# Nosumor.net
KiCad netlist of a schematic drawn in EAGLE
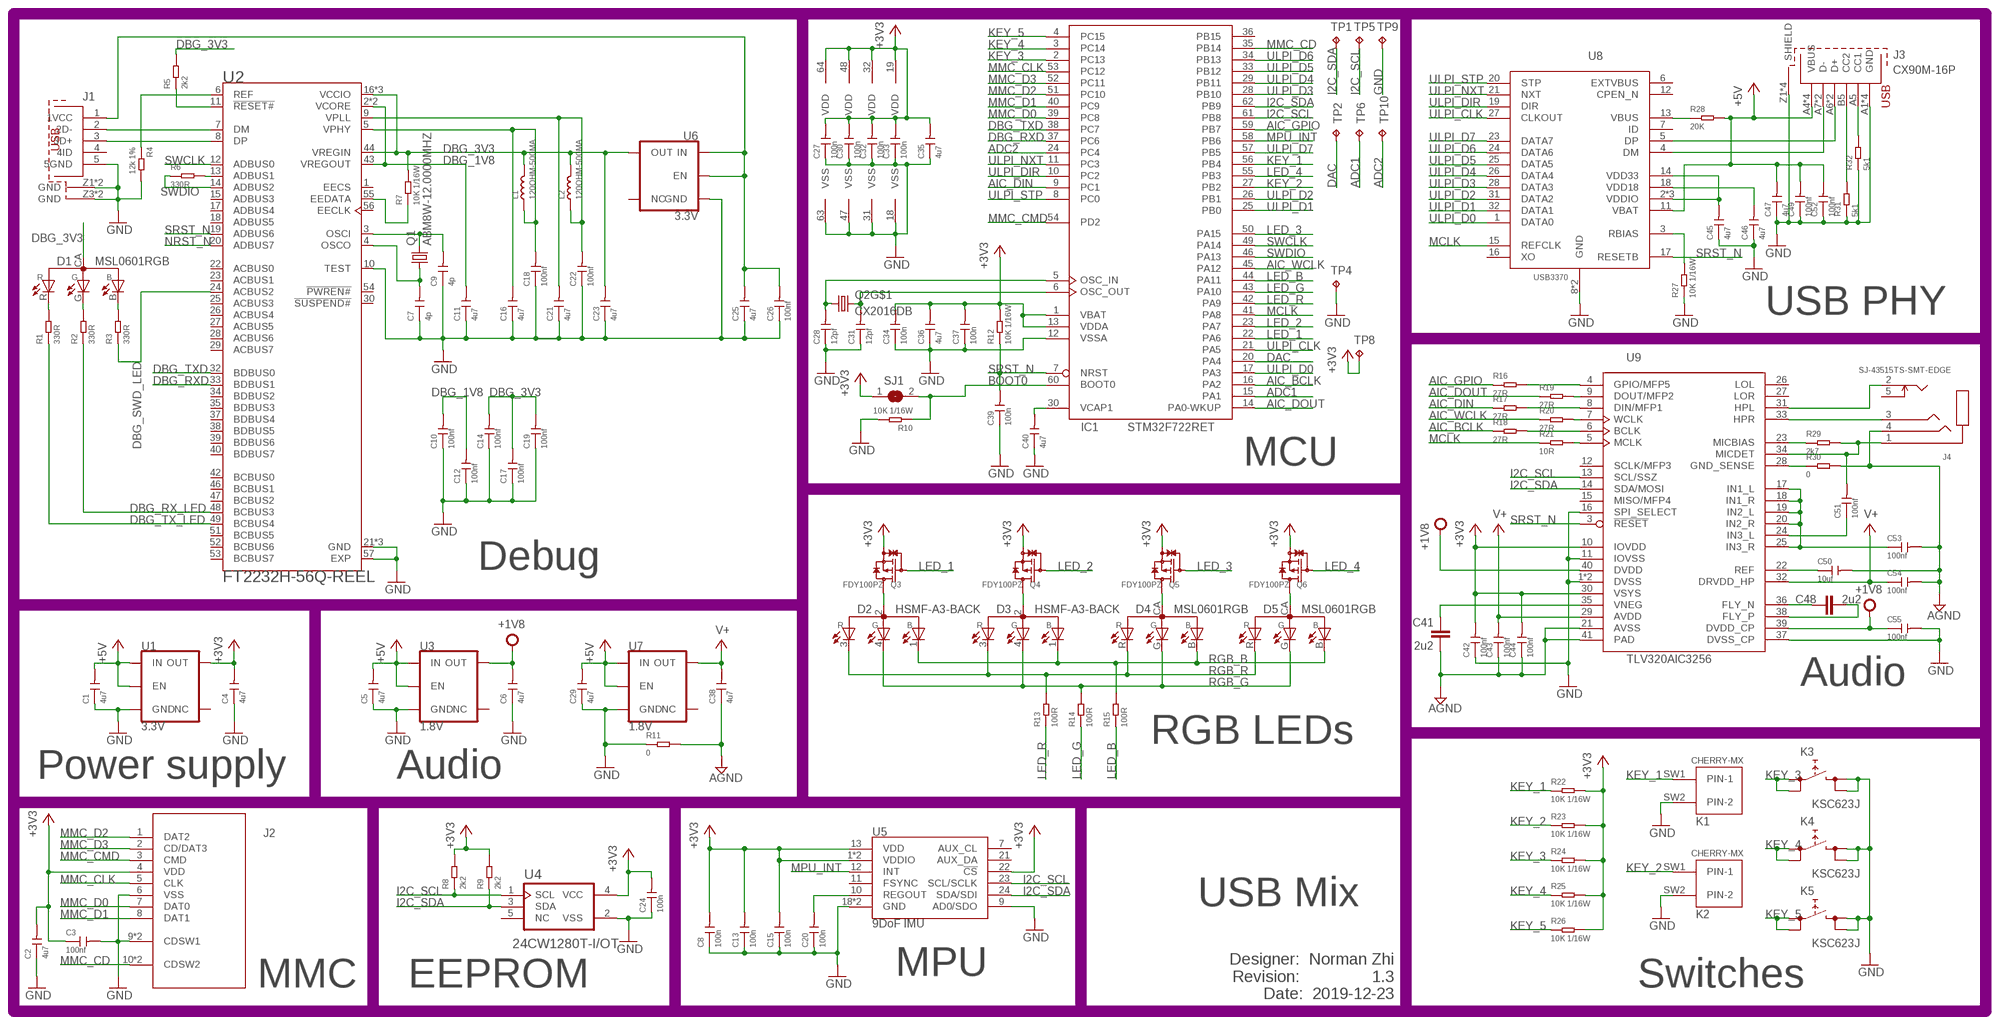
[diagram p0: schematic, sheet 1]

(export (version "E")
  (design (tool "Eeschema 10.0.6"))
  (components
    (comp (ref "C1")
      (value "4u7")
      (footprint "eagle-import:C0402")
      (fields (field (name "MPN") "CC0402KRX5R5BB105"))
      (libsource (lib "eagle-import") (part "CERAMIC-1UF-6.3V-10%-X5R(0402)"))
    )
    (comp (ref "C2")
      (value "4u7")
      (footprint "eagle-import:C0402")
      (fields (field (name "MPN") "CC0402KRX5R5BB105"))
      (libsource (lib "eagle-import") (part "CERAMIC-1UF-6.3V-10%-X5R(0402)"))
    )
    (comp (ref "C3")
      (value "100nf")
      (footprint "eagle-import:C0402")
      (fields (field (name "MPN") "CC0402KRX7R8BB104"))
      (libsource (lib "eagle-import") (part "CERAMIC-100NF-25V-10%-X7R(0402)"))
    )
    (comp (ref "C4")
      (value "4u7")
      (footprint "eagle-import:C0402")
      (fields (field (name "MPN") "CC0402KRX5R5BB105"))
      (libsource (lib "eagle-import") (part "CERAMIC-1UF-6.3V-10%-X5R(0402)"))
    )
    (comp (ref "C5")
      (value "4u7")
      (footprint "eagle-import:C0402")
      (fields (field (name "MPN") "CC0402KRX5R5BB105"))
      (libsource (lib "eagle-import") (part "CERAMIC-1UF-6.3V-10%-X5R(0402)"))
    )
    (comp (ref "C6")
      (value "4u7")
      (footprint "eagle-import:C0402")
      (fields (field (name "MPN") "CC0402KRX5R5BB105"))
      (libsource (lib "eagle-import") (part "CERAMIC-1UF-6.3V-10%-X5R(0402)"))
    )
    (comp (ref "C7")
      (value "4p")
      (footprint "eagle-import:C0402")
      (fields (field (name "MPN") "CC0402KRX7R8BB104"))
      (libsource (lib "eagle-import") (part "CERAMIC-100NF-25V-10%-X7R(0402)"))
    )
    (comp (ref "C8")
      (value "100n")
      (footprint "eagle-import:C0402")
      (fields (field (name "MPN") "CC0402KRX7R8BB104"))
      (libsource (lib "eagle-import") (part "CERAMIC-100NF-25V-10%-X7R(0402)"))
    )
    (comp (ref "C9")
      (value "4p")
      (footprint "eagle-import:C0402")
      (fields (field (name "MPN") "CC0402KRX7R8BB104"))
      (libsource (lib "eagle-import") (part "CERAMIC-100NF-25V-10%-X7R(0402)"))
    )
    (comp (ref "C10")
      (value "100nf")
      (footprint "eagle-import:C0402")
      (fields (field (name "MPN") "CC0402KRX7R8BB104"))
      (libsource (lib "eagle-import") (part "CERAMIC-100NF-25V-10%-X7R(0402)"))
    )
    (comp (ref "C11")
      (value "4u7")
      (footprint "eagle-import:C0402")
      (fields (field (name "MPN") "CC0402KRX7R8BB104"))
      (libsource (lib "eagle-import") (part "CERAMIC-100NF-25V-10%-X7R(0402)"))
    )
    (comp (ref "C12")
      (value "100nf")
      (footprint "eagle-import:C0402")
      (fields (field (name "MPN") "CC0402KRX7R8BB104"))
      (libsource (lib "eagle-import") (part "CERAMIC-100NF-25V-10%-X7R(0402)"))
    )
    (comp (ref "C13")
      (value "100n")
      (footprint "eagle-import:C0402")
      (fields (field (name "MPN") "CC0402KRX7R8BB104"))
      (libsource (lib "eagle-import") (part "CERAMIC-100NF-25V-10%-X7R(0402)"))
    )
    (comp (ref "C14")
      (value "100nf")
      (footprint "eagle-import:C0402")
      (fields (field (name "MPN") "CC0402KRX7R8BB104"))
      (libsource (lib "eagle-import") (part "CERAMIC-100NF-25V-10%-X7R(0402)"))
    )
    (comp (ref "C15")
      (value "100n")
      (footprint "eagle-import:C0402")
      (fields (field (name "MPN") "CC0402KRX7R9BB103"))
      (libsource (lib "eagle-import") (part "CERAMIC-10NF-50V-10%-X7R(0402)"))
    )
    (comp (ref "C16")
      (value "4u7")
      (footprint "eagle-import:C0402")
      (fields (field (name "MPN") "CC0402KRX7R8BB104"))
      (libsource (lib "eagle-import") (part "CERAMIC-100NF-25V-10%-X7R(0402)"))
    )
    (comp (ref "C17")
      (value "100nf")
      (footprint "eagle-import:C0402")
      (fields (field (name "MPN") "CC0402KRX7R8BB104"))
      (libsource (lib "eagle-import") (part "CERAMIC-100NF-25V-10%-X7R(0402)"))
    )
    (comp (ref "C18")
      (value "100nf")
      (footprint "eagle-import:C0402")
      (fields (field (name "MPN") "CC0402KRX7R8BB104"))
      (libsource (lib "eagle-import") (part "CERAMIC-100NF-25V-10%-X7R(0402)"))
    )
    (comp (ref "C19")
      (value "100nf")
      (footprint "eagle-import:C0402")
      (fields (field (name "MPN") "CC0402KRX7R8BB104"))
      (libsource (lib "eagle-import") (part "CERAMIC-100NF-25V-10%-X7R(0402)"))
    )
    (comp (ref "C20")
      (value "100n")
      (footprint "eagle-import:C0402")
      (fields (field (name "MPN") "CC0402KRX7R8BB104"))
      (libsource (lib "eagle-import") (part "CERAMIC-100NF-25V-10%-X7R(0402)"))
    )
    (comp (ref "C21")
      (value "4u7")
      (footprint "eagle-import:C0402")
      (fields (field (name "MPN") "CC0402KRX7R8BB104"))
      (libsource (lib "eagle-import") (part "CERAMIC-100NF-25V-10%-X7R(0402)"))
    )
    (comp (ref "C22")
      (value "100nf")
      (footprint "eagle-import:C0402")
      (fields (field (name "MPN") "CC0402KRX7R8BB104"))
      (libsource (lib "eagle-import") (part "CERAMIC-100NF-25V-10%-X7R(0402)"))
    )
    (comp (ref "C23")
      (value "4u7")
      (footprint "eagle-import:C0402")
      (fields (field (name "MPN") "CC0402KRX5R5BB105"))
      (libsource (lib "eagle-import") (part "CERAMIC-1UF-6.3V-10%-X5R(0402)"))
    )
    (comp (ref "C24")
      (value "100n")
      (footprint "eagle-import:C0402")
      (fields (field (name "MPN") "CC0402KRX7R8BB104"))
      (libsource (lib "eagle-import") (part "CERAMIC-100NF-25V-10%-X7R(0402)"))
    )
    (comp (ref "C25")
      (value "4u7")
      (footprint "eagle-import:C0402")
      (fields (field (name "MPN") "CC0402KRX5R5BB105"))
      (libsource (lib "eagle-import") (part "CERAMIC-1UF-6.3V-10%-X5R(0402)"))
    )
    (comp (ref "C26")
      (value "100nf")
      (footprint "eagle-import:C0402")
      (fields (field (name "MPN") "CC0402KRX7R8BB104"))
      (libsource (lib "eagle-import") (part "CERAMIC-100NF-25V-10%-X7R(0402)"))
    )
    (comp (ref "C27")
      (value "100n")
      (footprint "eagle-import:C0402")
      (fields (field (name "MPN") "CC0402KRX7R8BB104"))
      (libsource (lib "eagle-import") (part "CERAMIC-100NF-25V-10%-X7R(0402)"))
    )
    (comp (ref "C28")
      (value "12pf")
      (footprint "eagle-import:C0402")
      (fields (field (name "MPN") "CC0402JRNPO9BN120"))
      (libsource (lib "eagle-import") (part "CERAMIC-12PF-50V-5%-NPO(0402)"))
    )
    (comp (ref "C29")
      (value "4u7")
      (footprint "eagle-import:C0402")
      (fields (field (name "MPN") "CC0402KRX5R5BB105"))
      (libsource (lib "eagle-import") (part "CERAMIC-1UF-6.3V-10%-X5R(0402)"))
    )
    (comp (ref "C30")
      (value "100n")
      (footprint "eagle-import:C0402")
      (fields (field (name "MPN") "CC0402KRX7R8BB104"))
      (libsource (lib "eagle-import") (part "CERAMIC-100NF-25V-10%-X7R(0402)"))
    )
    (comp (ref "C31")
      (value "12pf")
      (footprint "eagle-import:C0402")
      (fields (field (name "MPN") "CC0402JRNPO9BN120"))
      (libsource (lib "eagle-import") (part "CERAMIC-12PF-50V-5%-NPO(0402)"))
    )
    (comp (ref "C32")
      (value "100n")
      (footprint "eagle-import:C0402")
      (fields (field (name "MPN") "CC0402KRX7R8BB104"))
      (libsource (lib "eagle-import") (part "CERAMIC-100NF-25V-10%-X7R(0402)"))
    )
    (comp (ref "C33")
      (value "100n")
      (footprint "eagle-import:C0402")
      (fields (field (name "MPN") "CC0402KRX7R8BB104"))
      (libsource (lib "eagle-import") (part "CERAMIC-100NF-25V-10%-X7R(0402)"))
    )
    (comp (ref "C34")
      (value "100n")
      (footprint "eagle-import:C0402")
      (fields (field (name "MPN") "CC0402KRX7R9BB103"))
      (libsource (lib "eagle-import") (part "CERAMIC-10NF-50V-10%-X7R(0402)"))
    )
    (comp (ref "C35")
      (value "4u7")
      (footprint "eagle-import:C0603")
      (fields (field (name "MPN") "CC0603KRX5R6BB475"))
      (libsource (lib "eagle-import") (part "CERAMIC-4.7UF-10V-10%-X5R(0603)"))
    )
    (comp (ref "C36")
      (value "4u7")
      (footprint "eagle-import:C0603")
      (fields (field (name "MPN") "CC0603KRX5R6BB475"))
      (libsource (lib "eagle-import") (part "CERAMIC-4.7UF-10V-10%-X5R(0603)"))
    )
    (comp (ref "C37")
      (value "100n")
      (footprint "eagle-import:C0402")
      (fields (field (name "MPN") "CC0402KRX7R8BB104"))
      (libsource (lib "eagle-import") (part "CERAMIC-100NF-25V-10%-X7R(0402)"))
    )
    (comp (ref "C38")
      (value "4u7")
      (footprint "eagle-import:C0402")
      (fields (field (name "MPN") "CC0402KRX5R5BB105"))
      (libsource (lib "eagle-import") (part "CERAMIC-1UF-6.3V-10%-X5R(0402)"))
    )
    (comp (ref "C39")
      (value "100n")
      (footprint "eagle-import:C0402")
      (fields (field (name "MPN") "CC0402KRX7R8BB104"))
      (libsource (lib "eagle-import") (part "CERAMIC-100NF-25V-10%-X7R(0402)"))
    )
    (comp (ref "C40")
      (value "4u7")
      (footprint "eagle-import:C0603")
      (fields (field (name "MPN") "CC0603KRX5R6BB475"))
      (libsource (lib "eagle-import") (part "CERAMIC-4.7UF-10V-10%-X5R(0603)"))
    )
    (comp (ref "C41")
      (value "2u2")
      (footprint "eagle-import:C0603K")
      (libsource (lib "eagle-import") (part "C-EUC0603K"))
    )
    (comp (ref "C42")
      (value "100nf")
      (footprint "eagle-import:C0402")
      (fields (field (name "MPN") "CC0402KRX7R8BB104"))
      (libsource (lib "eagle-import") (part "CERAMIC-100NF-25V-10%-X7R(0402)"))
    )
    (comp (ref "C43")
      (value "100nf")
      (footprint "eagle-import:C0402")
      (fields (field (name "MPN") "CC0402KRX7R8BB104"))
      (libsource (lib "eagle-import") (part "CERAMIC-100NF-25V-10%-X7R(0402)"))
    )
    (comp (ref "C44")
      (value "100nf")
      (footprint "eagle-import:C0402")
      (fields (field (name "MPN") "CC0402KRX7R8BB104"))
      (libsource (lib "eagle-import") (part "CERAMIC-100NF-25V-10%-X7R(0402)"))
    )
    (comp (ref "C45")
      (value "4u7")
      (footprint "eagle-import:C0402")
      (fields (field (name "MPN") "CC0402KRX5R5BB105"))
      (libsource (lib "eagle-import") (part "CERAMIC-1UF-6.3V-10%-X5R(0402)"))
    )
    (comp (ref "C46")
      (value "4u7")
      (footprint "eagle-import:C0402")
      (fields (field (name "MPN") "CC0402KRX5R5BB105"))
      (libsource (lib "eagle-import") (part "CERAMIC-1UF-6.3V-10%-X5R(0402)"))
    )
    (comp (ref "C47")
      (value "4u7")
      (footprint "eagle-import:C0402")
      (fields (field (name "MPN") "CC0402KRX5R5BB105"))
      (libsource (lib "eagle-import") (part "CERAMIC-1UF-6.3V-10%-X5R(0402)"))
    )
    (comp (ref "C48")
      (value "2u2")
      (footprint "eagle-import:C0603K")
      (libsource (lib "eagle-import") (part "C-EUC0603K"))
    )
    (comp (ref "C49")
      (value "100nf")
      (footprint "eagle-import:C0402")
      (fields (field (name "MPN") "CC0402KRX7R8BB104"))
      (libsource (lib "eagle-import") (part "CERAMIC-100NF-25V-10%-X7R(0402)"))
    )
    (comp (ref "C50")
      (value "10uf")
      (footprint "eagle-import:C0603")
      (fields (field (name "MPN") "CC0603KRX5R6BB106"))
      (libsource (lib "eagle-import") (part "CERAMIC-10UF-10V-10%-X5R(0603)"))
    )
    (comp (ref "C51")
      (value "100nf")
      (footprint "eagle-import:C0402")
      (fields (field (name "MPN") "CC0402KRX7R8BB104"))
      (libsource (lib "eagle-import") (part "CERAMIC-100NF-25V-10%-X7R(0402)"))
    )
    (comp (ref "C52")
      (value "100nf")
      (footprint "eagle-import:C0402")
      (fields (field (name "MPN") "CC0402KRX7R8BB104"))
      (libsource (lib "eagle-import") (part "CERAMIC-100NF-25V-10%-X7R(0402)"))
    )
    (comp (ref "C53")
      (value "100nf")
      (footprint "eagle-import:C0402")
      (fields (field (name "MPN") "CC0402KRX7R8BB104"))
      (libsource (lib "eagle-import") (part "CERAMIC-100NF-25V-10%-X7R(0402)"))
    )
    (comp (ref "C54")
      (value "100nf")
      (footprint "eagle-import:C0402")
      (fields (field (name "MPN") "CC0402KRX7R8BB104"))
      (libsource (lib "eagle-import") (part "CERAMIC-100NF-25V-10%-X7R(0402)"))
    )
    (comp (ref "C55")
      (value "100nf")
      (footprint "eagle-import:C0402")
      (fields (field (name "MPN") "CC0402KRX7R8BB104"))
      (libsource (lib "eagle-import") (part "CERAMIC-100NF-25V-10%-X7R(0402)"))
    )
    (comp (ref "D1")
      (value "MSL0601RGB")
      (footprint "eagle-import:1105")
      (libsource (lib "eagle-import") (part "MSL0601RGB"))
    )
    (comp (ref "D2")
      (value "HSMF-A3-BACK")
      (footprint "eagle-import:HSMF-A3-BACK")
      (libsource (lib "eagle-import") (part "HSMF-A3-BACK"))
    )
    (comp (ref "D3")
      (value "HSMF-A3-BACK")
      (footprint "eagle-import:HSMF-A3-BACK")
      (libsource (lib "eagle-import") (part "HSMF-A3-BACK"))
    )
    (comp (ref "D4")
      (value "MSL0601RGB")
      (footprint "eagle-import:1105")
      (libsource (lib "eagle-import") (part "MSL0601RGB"))
    )
    (comp (ref "D5")
      (value "MSL0601RGB")
      (footprint "eagle-import:1105")
      (libsource (lib "eagle-import") (part "MSL0601RGB"))
    )
    (comp (ref "IC1")
      (value "STM32F722RET")
      (footprint "eagle-import:LQFP64")
      (libsource (lib "eagle-import") (part "STM32F722RTE"))
    )
    (comp (ref "J1")
      (value "629105150521")
      (footprint "eagle-import:629105150521")
      (libsource (lib "eagle-import") (part "629105150521"))
    )
    (comp (ref "J2")
      (value "693071010811")
      (footprint "eagle-import:693071010811")
      (libsource (lib "eagle-import") (part "693071010811"))
    )
    (comp (ref "J3")
      (value "CX90M-16P")
      (footprint "eagle-import:CX90M-16P")
      (libsource (lib "eagle-import") (part "CX90M-16P"))
    )
    (comp (ref "J4")
      (value "SJ-43515TS-SMT-EDGE")
      (footprint "eagle-import:SJ-4351_-SMT-MIRRORED-EDGE")
      (libsource (lib "eagle-import") (part "SJ-43515TS-SMT-EDGE"))
    )
    (comp (ref "K1")
      (value "CHERRY-MX")
      (footprint "eagle-import:CHERRY-MX")
      (libsource (lib "eagle-import") (part "CHERRY-MX"))
    )
    (comp (ref "K2")
      (value "CHERRY-MX")
      (footprint "eagle-import:CHERRY-MX")
      (libsource (lib "eagle-import") (part "CHERRY-MX"))
    )
    (comp (ref "K3")
      (value "KSC623J")
      (footprint "eagle-import:KSC-J")
      (libsource (lib "eagle-import") (part "KSCJ623"))
    )
    (comp (ref "K4")
      (value "KSC623J")
      (footprint "eagle-import:KSC-J")
      (libsource (lib "eagle-import") (part "KSCJ623"))
    )
    (comp (ref "K5")
      (value "KSC623J")
      (footprint "eagle-import:KSC-J")
      (libsource (lib "eagle-import") (part "KSCJ623"))
    )
    (comp (ref "L1")
      (value "120OHM-500MA")
      (footprint "eagle-import:L0603")
      (fields (field (name "MPN") "BLM18AG121SN1D"))
      (libsource (lib "eagle-import") (part "SMD-FERRITE-CHIP-120-OHM-500MA(0603)"))
    )
    (comp (ref "L2")
      (value "120OHM-500MA")
      (footprint "eagle-import:L0603")
      (fields (field (name "MPN") "BLM18AG121SN1D"))
      (libsource (lib "eagle-import") (part "SMD-FERRITE-CHIP-120-OHM-500MA(0603)"))
    )
    (comp (ref "Q1")
      (value "ABM8W-12.0000MHZ")
      (footprint "eagle-import:ABM8W")
      (libsource (lib "eagle-import") (part "ABM?-MHZ8W12.0000"))
    )
    (comp (ref "Q2")
      (value "CX2016DB")
      (footprint "eagle-import:CX2016DB")
      (libsource (lib "eagle-import") (part "CX2016DB"))
    )
    (comp (ref "Q3")
      (value "FDY100PZ")
      (footprint "eagle-import:SC-89")
      (libsource (lib "eagle-import") (part "FDY100PZ"))
    )
    (comp (ref "Q4")
      (value "FDY100PZ")
      (footprint "eagle-import:SC-89")
      (libsource (lib "eagle-import") (part "FDY100PZ"))
    )
    (comp (ref "Q5")
      (value "FDY100PZ")
      (footprint "eagle-import:SC-89")
      (libsource (lib "eagle-import") (part "FDY100PZ"))
    )
    (comp (ref "Q6")
      (value "FDY100PZ")
      (footprint "eagle-import:SC-89")
      (libsource (lib "eagle-import") (part "FDY100PZ"))
    )
    (comp (ref "R1")
      (value "330R")
      (footprint "eagle-import:R0402")
      (fields (field (name "MPN") "RC0402FR-07330RL"))
      (libsource (lib "eagle-import") (part "SMD-RES-330R-1%-1/16W(0402)"))
    )
    (comp (ref "R2")
      (value "330R")
      (footprint "eagle-import:R0402")
      (fields (field (name "MPN") "RC0402FR-07330RL"))
      (libsource (lib "eagle-import") (part "SMD-RES-330R-1%-1/16W(0402)"))
    )
    (comp (ref "R3")
      (value "330R")
      (footprint "eagle-import:R0402")
      (fields (field (name "MPN") "RC0402FR-07330RL"))
      (libsource (lib "eagle-import") (part "SMD-RES-330R-1%-1/16W(0402)"))
    )
    (comp (ref "R4")
      (value "12k 1%")
      (footprint "eagle-import:R0402")
      (fields (field (name "MPN") "RC0402FR-0710KL"))
      (libsource (lib "eagle-import") (part "SMD-RES-10K-1%-1/16W(0402)"))
    )
    (comp (ref "R5")
      (value "2k2")
      (footprint "eagle-import:R0402")
      (fields (field (name "MPN") "RC0402FR-0710KL"))
      (libsource (lib "eagle-import") (part "SMD-RES-10K-1%-1/16W(0402)"))
    )
    (comp (ref "R6")
      (value "330R")
      (footprint "eagle-import:R0402")
      (fields (field (name "MPN") "RC0402JR-07470RL"))
      (libsource (lib "eagle-import") (part "SMD-RES-470R-5%-1/16W(0402)"))
    )
    (comp (ref "R7")
      (value "10K 1/16W")
      (footprint "eagle-import:R0402")
      (fields (field (name "MPN") "RC0402FR-0710KL"))
      (libsource (lib "eagle-import") (part "SMD-RES-10K-1%-1/16W(0402)"))
    )
    (comp (ref "R8")
      (value "2k2")
      (footprint "eagle-import:R0402")
      (fields (field (name "MPN") "RC0402FR-0710KL"))
      (libsource (lib "eagle-import") (part "SMD-RES-10K-1%-1/16W(0402)"))
    )
    (comp (ref "R9")
      (value "2k2")
      (footprint "eagle-import:R0402")
      (fields (field (name "MPN") "RC0402FR-0710KL"))
      (libsource (lib "eagle-import") (part "SMD-RES-10K-1%-1/16W(0402)"))
    )
    (comp (ref "R10")
      (value "10K 1/16W")
      (footprint "eagle-import:R0402")
      (fields (field (name "MPN") "RC0402FR-0710KL"))
      (libsource (lib "eagle-import") (part "SMD-RES-10K-1%-1/16W(0402)"))
    )
    (comp (ref "R11")
      (value "0")
      (footprint "eagle-import:R0402")
      (fields (field (name "MPN") "RC0402JR-071KL"))
      (libsource (lib "eagle-import") (part "SMD-RES-1K-5%-1/16W(0402)"))
    )
    (comp (ref "R12")
      (value "10K 1/16W")
      (footprint "eagle-import:R0402")
      (fields (field (name "MPN") "RC0402FR-0710KL"))
      (libsource (lib "eagle-import") (part "SMD-RES-10K-1%-1/16W(0402)"))
    )
    (comp (ref "R13")
      (value "100R")
      (footprint "eagle-import:R0402")
      (fields (field (name "MPN") "RC0402FR-07330RL"))
      (libsource (lib "eagle-import") (part "SMD-RES-330R-1%-1/16W(0402)"))
    )
    (comp (ref "R14")
      (value "100R")
      (footprint "eagle-import:R0402")
      (fields (field (name "MPN") "RC0402FR-07330RL"))
      (libsource (lib "eagle-import") (part "SMD-RES-330R-1%-1/16W(0402)"))
    )
    (comp (ref "R15")
      (value "100R")
      (footprint "eagle-import:R0402")
      (fields (field (name "MPN") "RC0402FR-07330RL"))
      (libsource (lib "eagle-import") (part "SMD-RES-330R-1%-1/16W(0402)"))
    )
    (comp (ref "R16")
      (value "27R")
      (footprint "eagle-import:R0402")
      (fields (field (name "MPN") "RC0402FR-07330RL"))
      (libsource (lib "eagle-import") (part "SMD-RES-330R-1%-1/16W(0402)"))
    )
    (comp (ref "R17")
      (value "27R")
      (footprint "eagle-import:R0402")
      (fields (field (name "MPN") "RC0402FR-07330RL"))
      (libsource (lib "eagle-import") (part "SMD-RES-330R-1%-1/16W(0402)"))
    )
    (comp (ref "R18")
      (value "27R")
      (footprint "eagle-import:R0402")
      (fields (field (name "MPN") "RC0402FR-07330RL"))
      (libsource (lib "eagle-import") (part "SMD-RES-330R-1%-1/16W(0402)"))
    )
    (comp (ref "R19")
      (value "27R")
      (footprint "eagle-import:R0402")
      (fields (field (name "MPN") "RC0402FR-07330RL"))
      (libsource (lib "eagle-import") (part "SMD-RES-330R-1%-1/16W(0402)"))
    )
    (comp (ref "R20")
      (value "27R")
      (footprint "eagle-import:R0402")
      (fields (field (name "MPN") "RC0402FR-07330RL"))
      (libsource (lib "eagle-import") (part "SMD-RES-330R-1%-1/16W(0402)"))
    )
    (comp (ref "R21")
      (value "10R")
      (footprint "eagle-import:R0402")
      (fields (field (name "MPN") "RC0402FR-07330RL"))
      (libsource (lib "eagle-import") (part "SMD-RES-330R-1%-1/16W(0402)"))
    )
    (comp (ref "R22")
      (value "10K 1/16W")
      (footprint "eagle-import:R0402")
      (fields (field (name "MPN") "RC0402FR-0710KL"))
      (libsource (lib "eagle-import") (part "SMD-RES-10K-1%-1/16W(0402)"))
    )
    (comp (ref "R23")
      (value "10K 1/16W")
      (footprint "eagle-import:R0402")
      (fields (field (name "MPN") "RC0402FR-0710KL"))
      (libsource (lib "eagle-import") (part "SMD-RES-10K-1%-1/16W(0402)"))
    )
    (comp (ref "R24")
      (value "10K 1/16W")
      (footprint "eagle-import:R0402")
      (fields (field (name "MPN") "RC0402FR-0710KL"))
      (libsource (lib "eagle-import") (part "SMD-RES-10K-1%-1/16W(0402)"))
    )
    (comp (ref "R25")
      (value "10K 1/16W")
      (footprint "eagle-import:R0402")
      (fields (field (name "MPN") "RC0402FR-0710KL"))
      (libsource (lib "eagle-import") (part "SMD-RES-10K-1%-1/16W(0402)"))
    )
    (comp (ref "R26")
      (value "10K 1/16W")
      (footprint "eagle-import:R0402")
      (fields (field (name "MPN") "RC0402FR-0710KL"))
      (libsource (lib "eagle-import") (part "SMD-RES-10K-1%-1/16W(0402)"))
    )
    (comp (ref "R27")
      (value "10K 1/16W")
      (footprint "eagle-import:R0402")
      (fields (field (name "MPN") "RC0402FR-0710KL"))
      (libsource (lib "eagle-import") (part "SMD-RES-10K-1%-1/16W(0402)"))
    )
    (comp (ref "R28")
      (value "20K")
      (footprint "eagle-import:R0402")
      (fields (field (name "MPN") "RC0402JR-071KL"))
      (libsource (lib "eagle-import") (part "SMD-RES-1K-5%-1/16W(0402)"))
    )
    (comp (ref "R29")
      (value "2k7")
      (footprint "eagle-import:R0402")
      (fields (field (name "MPN") "RC0402JR-071KL"))
      (libsource (lib "eagle-import") (part "SMD-RES-1K-5%-1/16W(0402)"))
    )
    (comp (ref "R30")
      (value "0")
      (footprint "eagle-import:R0402")
      (fields (field (name "MPN") "RC0402JR-071KL"))
      (libsource (lib "eagle-import") (part "SMD-RES-1K-5%-1/16W(0402)"))
    )
    (comp (ref "R31")
      (value "5k1")
      (footprint "eagle-import:R0402")
      (fields (field (name "MPN") "RC0402JR-071KL"))
      (libsource (lib "eagle-import") (part "SMD-RES-1K-5%-1/16W(0402)"))
    )
    (comp (ref "R32")
      (value "5k1")
      (footprint "eagle-import:R0402")
      (fields (field (name "MPN") "RC0402JR-071KL"))
      (libsource (lib "eagle-import") (part "SMD-RES-1K-5%-1/16W(0402)"))
    )
    (comp (ref "SJ1") (value "SJ") (footprint "eagle-import:SJ") (libsource (lib "eagle-import") (part "SJ")))
    (comp (ref "TP1")
      (value "TPB1,27")
      (footprint "eagle-import:B1,27")
      (libsource (lib "eagle-import") (part "TPB1,27"))
    )
    (comp (ref "TP2")
      (value "TPB1,27")
      (footprint "eagle-import:B1,27")
      (libsource (lib "eagle-import") (part "TPB1,27"))
    )
    (comp (ref "TP4")
      (value "TPB1,27")
      (footprint "eagle-import:B1,27")
      (libsource (lib "eagle-import") (part "TPB1,27"))
    )
    (comp (ref "TP5")
      (value "TPB1,27")
      (footprint "eagle-import:B1,27")
      (libsource (lib "eagle-import") (part "TPB1,27"))
    )
    (comp (ref "TP6")
      (value "TPB1,27")
      (footprint "eagle-import:B1,27")
      (libsource (lib "eagle-import") (part "TPB1,27"))
    )
    (comp (ref "TP8")
      (value "TPB1,27")
      (footprint "eagle-import:B1,27")
      (libsource (lib "eagle-import") (part "TPB1,27"))
    )
    (comp (ref "TP9")
      (value "TPB1,27")
      (footprint "eagle-import:B1,27")
      (libsource (lib "eagle-import") (part "TPB1,27"))
    )
    (comp (ref "TP10")
      (value "TPB1,27")
      (footprint "eagle-import:B1,27")
      (libsource (lib "eagle-import") (part "TPB1,27"))
    )
    (comp (ref "U1")
      (value "3.3V")
      (footprint "eagle-import:SOT23-5")
      (libsource (lib "eagle-import") (part "V_REG_AP2112K-3.3V"))
    )
    (comp (ref "U2")
      (value "FT2232H-56Q-REEL")
      (footprint "eagle-import:QFN50P800X800X100-57N")
      (fields (field (name "DIGI-KEY_PART_NUMBER") "FT2232H-56Q-REEL-ND") (field (name "MF") "FTDI,"))
      (libsource (lib "eagle-import") (part "FT2232H-56Q-REEL"))
    )
    (comp (ref "U3")
      (value "1.8V")
      (footprint "eagle-import:SOT23-5")
      (libsource (lib "eagle-import") (part "V_REG_AP2112K-3.3V"))
    )
    (comp (ref "U4")
      (value "24CW1280T-I/OT")
      (footprint "eagle-import:SOT95P280X145-5N")
      (fields (field (name "MF") "Microchip"))
      (libsource (lib "eagle-import") (part "24CW1280T-I/OT"))
    )
    (comp (ref "U5")
      (value "9DoF IMU")
      (footprint "eagle-import:QFN24-3X3")
      (libsource (lib "eagle-import") (part "MPU-9250"))
    )
    (comp (ref "U6")
      (value "3.3V")
      (footprint "eagle-import:SOT23-5")
      (libsource (lib "eagle-import") (part "V_REG_AP2112K-3.3V"))
    )
    (comp (ref "U7")
      (value "1.8V")
      (footprint "eagle-import:SOT23-5")
      (libsource (lib "eagle-import") (part "V_REG_AP2112K-3.3V"))
    )
    (comp (ref "U8")
      (value "USB3370")
      (footprint "eagle-import:QFN32")
      (libsource (lib "eagle-import") (part "USB3370"))
    )
    (comp (ref "U9")
      (value "TLV320AIC3256")
      (footprint "eagle-import:QFN40P500X500X80-41N")
      (libsource (lib "eagle-import") (part "TLV320AIC3256"))
    )
  )
  (nets
    (net (code "1") (name "+1V8") (class "Default")
      (node (ref "C55") (pin "1") (pinfunction "1_1") (pintype "passive"))
      (node (ref "C6") (pin "2") (pinfunction "2_2") (pintype "passive"))
      (node (ref "U3") (pin "5") (pinfunction "OUT_5") (pintype "passive"))
      (node (ref "U9") (pin "39") (pinfunction "DVDD_CP_39") (pintype "bidirectional"))
      (node (ref "U9") (pin "40") (pinfunction "DVDD_40") (pintype "bidirectional"))
    )
    (net (code "2") (name "+3V3") (class "Default")
      (node (ref "C13") (pin "2") (pinfunction "2_2") (pintype "passive"))
      (node (ref "C15") (pin "2") (pinfunction "2_2") (pintype "passive"))
      (node (ref "C2") (pin "2") (pinfunction "2_2") (pintype "passive"))
      (node (ref "C24") (pin "2") (pinfunction "2_2") (pintype "passive"))
      (node (ref "C27") (pin "2") (pinfunction "2_2") (pintype "passive"))
      (node (ref "C3") (pin "1") (pinfunction "1_1") (pintype "passive"))
      (node (ref "C30") (pin "2") (pinfunction "2_2") (pintype "passive"))
      (node (ref "C32") (pin "2") (pinfunction "2_2") (pintype "passive"))
      (node (ref "C33") (pin "2") (pinfunction "2_2") (pintype "passive"))
      (node (ref "C34") (pin "2") (pinfunction "2_2") (pintype "passive"))
      (node (ref "C35") (pin "2") (pinfunction "2_2") (pintype "passive"))
      (node (ref "C36") (pin "2") (pinfunction "2_2") (pintype "passive"))
      (node (ref "C37") (pin "2") (pinfunction "2_2") (pintype "passive"))
      (node (ref "C4") (pin "2") (pinfunction "2_2") (pintype "passive"))
      (node (ref "C42") (pin "2") (pinfunction "2_2") (pintype "passive"))
      (node (ref "C44") (pin "2") (pinfunction "2_2") (pintype "passive"))
      (node (ref "C8") (pin "2") (pinfunction "2_2") (pintype "passive"))
      (node (ref "IC1") (pin "1") (pinfunction "VBAT_1") (pintype "power_in"))
      (node (ref "IC1") (pin "13") (pinfunction "VDDA_13") (pintype "power_in"))
      (node (ref "IC1") (pin "19") (pinfunction "VDD_19") (pintype "power_in"))
      (node (ref "IC1") (pin "32") (pinfunction "VDD_32") (pintype "power_in"))
      (node (ref "IC1") (pin "48") (pinfunction "VDD_48") (pintype "power_in"))
      (node (ref "IC1") (pin "64") (pinfunction "VDD_64") (pintype "power_in"))
      (node (ref "J2") (pin "4") (pinfunction "VDD_4") (pintype "bidirectional"))
      (node (ref "Q3") (pin "3") (pinfunction "S_3") (pintype "passive"))
      (node (ref "Q4") (pin "3") (pinfunction "S_3") (pintype "passive"))
      (node (ref "Q5") (pin "3") (pinfunction "S_3") (pintype "passive"))
      (node (ref "Q6") (pin "3") (pinfunction "S_3") (pintype "passive"))
      (node (ref "R12") (pin "2") (pinfunction "2_2") (pintype "passive"))
      (node (ref "R22") (pin "2") (pinfunction "2_2") (pintype "passive"))
      (node (ref "R23") (pin "2") (pinfunction "2_2") (pintype "passive"))
      (node (ref "R24") (pin "2") (pinfunction "2_2") (pintype "passive"))
      (node (ref "R25") (pin "2") (pinfunction "2_2") (pintype "passive"))
      (node (ref "R26") (pin "2") (pinfunction "2_2") (pintype "passive"))
      (node (ref "R8") (pin "2") (pinfunction "2_2") (pintype "passive"))
      (node (ref "R9") (pin "2") (pinfunction "2_2") (pintype "passive"))
      (node (ref "SJ1") (pin "1") (pinfunction "1_1") (pintype "passive"))
      (node (ref "TP8") (pin "TP") (pinfunction "TP_TP") (pintype "input"))
      (node (ref "U1") (pin "5") (pinfunction "OUT_5") (pintype "passive"))
      (node (ref "U4") (pin "4") (pinfunction "VCC_4") (pintype "power_in"))
      (node (ref "U5") (pin "1") (pinfunction "VDDIO_1") (pintype "bidirectional"))
      (node (ref "U5") (pin "13") (pinfunction "VDD_13") (pintype "bidirectional"))
      (node (ref "U5") (pin "22") (pinfunction "~{CS}_22") (pintype "bidirectional"))
      (node (ref "U5") (pin "8") (pinfunction "VDDIO_8") (pintype "bidirectional"))
      (node (ref "U9") (pin "10") (pinfunction "IOVDD_10") (pintype "bidirectional"))
      (node (ref "U9") (pin "30") (pinfunction "VSYS_30") (pintype "bidirectional"))
    )
    (net (code "3") (name "+5V") (class "Default")
      (node (ref "C1") (pin "2") (pinfunction "2_2") (pintype "passive"))
      (node (ref "C29") (pin "2") (pinfunction "2_2") (pintype "passive"))
      (node (ref "C47") (pin "2") (pinfunction "2_2") (pintype "passive"))
      (node (ref "C49") (pin "2") (pinfunction "2_2") (pintype "passive"))
      (node (ref "C5") (pin "2") (pinfunction "2_2") (pintype "passive"))
      (node (ref "C52") (pin "2") (pinfunction "2_2") (pintype "passive"))
      (node (ref "J3") (pin "A4") (pinfunction "VBUS_A4") (pintype "passive"))
      (node (ref "J3") (pin "A9") (pinfunction "VBUS_A9") (pintype "passive"))
      (node (ref "J3") (pin "B4") (pinfunction "VBUS_B4") (pintype "passive"))
      (node (ref "J3") (pin "B9") (pinfunction "VBUS_B9") (pintype "passive"))
      (node (ref "R28") (pin "2") (pinfunction "2_2") (pintype "passive"))
      (node (ref "U1") (pin "1") (pinfunction "IN_1") (pintype "input"))
      (node (ref "U1") (pin "3") (pinfunction "EN_3") (pintype "input"))
      (node (ref "U3") (pin "1") (pinfunction "IN_1") (pintype "input"))
      (node (ref "U3") (pin "3") (pinfunction "EN_3") (pintype "input"))
      (node (ref "U7") (pin "1") (pinfunction "IN_1") (pintype "input"))
      (node (ref "U7") (pin "3") (pinfunction "EN_3") (pintype "input"))
      (node (ref "U8") (pin "11") (pinfunction "VBAT_11") (pintype "bidirectional"))
    )
    (net (code "4") (name "/ADC1") (class "Default")
      (node (ref "IC1") (pin "15") (pinfunction "PA1_15") (pintype "bidirectional"))
      (node (ref "TP6") (pin "TP") (pinfunction "TP_TP") (pintype "input"))
    )
    (net (code "5") (name "/ADC2") (class "Default")
      (node (ref "IC1") (pin "24") (pinfunction "PC4_24") (pintype "bidirectional"))
      (node (ref "TP10") (pin "TP") (pinfunction "TP_TP") (pintype "input"))
    )
    (net (code "6") (name "/AIC_BCLK") (class "Default")
      (node (ref "IC1") (pin "16") (pinfunction "PA2_16") (pintype "bidirectional"))
      (node (ref "R18") (pin "1") (pinfunction "1_1") (pintype "passive"))
    )
    (net (code "7") (name "/AIC_DIN") (class "Default")
      (node (ref "IC1") (pin "9") (pinfunction "PC1_9") (pintype "bidirectional"))
      (node (ref "R17") (pin "1") (pinfunction "1_1") (pintype "passive"))
    )
    (net (code "8") (name "/AIC_DOUT") (class "Default")
      (node (ref "IC1") (pin "14") (pinfunction "PA0-WKUP_14") (pintype "bidirectional"))
      (node (ref "R19") (pin "1") (pinfunction "1_1") (pintype "passive"))
    )
    (net (code "9") (name "/AIC_GPIO") (class "Default")
      (node (ref "IC1") (pin "59") (pinfunction "PB7_59") (pintype "bidirectional"))
      (node (ref "R16") (pin "1") (pinfunction "1_1") (pintype "passive"))
    )
    (net (code "10") (name "/AIC_WCLK") (class "Default")
      (node (ref "IC1") (pin "45") (pinfunction "PA12_45") (pintype "bidirectional"))
      (node (ref "R20") (pin "1") (pinfunction "1_1") (pintype "passive"))
    )
    (net (code "11") (name "/BOOT0") (class "Default")
      (node (ref "IC1") (pin "60") (pinfunction "BOOT0_60") (pintype "input"))
      (node (ref "R10") (pin "1") (pinfunction "1_1") (pintype "passive"))
      (node (ref "SJ1") (pin "2") (pinfunction "2_2") (pintype "passive"))
    )
    (net (code "12") (name "/DAC") (class "Default")
      (node (ref "IC1") (pin "20") (pinfunction "PA4_20") (pintype "bidirectional"))
      (node (ref "TP2") (pin "TP") (pinfunction "TP_TP") (pintype "input"))
    )
    (net (code "13") (name "/DBG_1V8") (class "Default")
      (node (ref "C10") (pin "2") (pinfunction "2_2") (pintype "passive"))
      (node (ref "C11") (pin "2") (pinfunction "2_2") (pintype "passive"))
      (node (ref "C12") (pin "2") (pinfunction "2_2") (pintype "passive"))
      (node (ref "U2") (pin "2") (pinfunction "VCORE_2") (pintype "power_in"))
      (node (ref "U2") (pin "31") (pinfunction "VCORE_31") (pintype "power_in"))
      (node (ref "U2") (pin "43") (pinfunction "VREGOUT_43") (pintype "power_in"))
    )
    (net (code "14") (name "/DBG_3V3") (class "Default")
      (node (ref "C14") (pin "2") (pinfunction "2_2") (pintype "passive"))
      (node (ref "C17") (pin "2") (pinfunction "2_2") (pintype "passive"))
      (node (ref "C19") (pin "2") (pinfunction "2_2") (pintype "passive"))
      (node (ref "C23") (pin "2") (pinfunction "2_2") (pintype "passive"))
      (node (ref "D1") (pin "CA") (pinfunction "A_CA") (pintype "bidirectional"))
      (node (ref "L1") (pin "2") (pinfunction "2_2") (pintype "passive"))
      (node (ref "L2") (pin "2") (pinfunction "2_2") (pintype "passive"))
      (node (ref "R5") (pin "2") (pinfunction "2_2") (pintype "passive"))
      (node (ref "R7") (pin "2") (pinfunction "2_2") (pintype "passive"))
      (node (ref "U2") (pin "16") (pinfunction "VCCIO_16") (pintype "power_in"))
      (node (ref "U2") (pin "36") (pinfunction "VCCIO_36") (pintype "power_in"))
      (node (ref "U2") (pin "44") (pinfunction "VREGIN_44") (pintype "power_in"))
      (node (ref "U2") (pin "50") (pinfunction "VCCIO_50") (pintype "power_in"))
      (node (ref "U6") (pin "5") (pinfunction "OUT_5") (pintype "passive"))
    )
    (net (code "15") (name "/DBG_RXD") (class "Default")
      (node (ref "IC1") (pin "37") (pinfunction "PC6_37") (pintype "bidirectional"))
      (node (ref "U2") (pin "33") (pinfunction "BDBUS1_33") (pintype "bidirectional"))
    )
    (net (code "16") (name "/DBG_RX_LED") (class "Default")
      (node (ref "R2") (pin "1") (pinfunction "1_1") (pintype "passive"))
      (node (ref "U2") (pin "48") (pinfunction "BCBUS3_48") (pintype "bidirectional"))
    )
    (net (code "17") (name "/DBG_SWD_LED") (class "Default")
      (node (ref "R3") (pin "1") (pinfunction "1_1") (pintype "passive"))
      (node (ref "U2") (pin "24") (pinfunction "ACBUS2_24") (pintype "bidirectional"))
    )
    (net (code "18") (name "/DBG_TXD") (class "Default")
      (node (ref "IC1") (pin "38") (pinfunction "PC7_38") (pintype "bidirectional"))
      (node (ref "U2") (pin "32") (pinfunction "BDBUS0_32") (pintype "bidirectional"))
    )
    (net (code "19") (name "/DBG_TX_LED") (class "Default")
      (node (ref "R1") (pin "1") (pinfunction "1_1") (pintype "passive"))
      (node (ref "U2") (pin "49") (pinfunction "BCBUS4_49") (pintype "bidirectional"))
    )
    (net (code "20") (name "/I2C_SCL") (class "Default")
      (node (ref "IC1") (pin "61") (pinfunction "PB8_61") (pintype "bidirectional"))
      (node (ref "R8") (pin "1") (pinfunction "1_1") (pintype "passive"))
      (node (ref "TP5") (pin "TP") (pinfunction "TP_TP") (pintype "input"))
      (node (ref "U4") (pin "1") (pinfunction "SCL_1") (pintype "input"))
      (node (ref "U5") (pin "23") (pinfunction "SCL/SCLK_23") (pintype "bidirectional"))
      (node (ref "U9") (pin "13") (pinfunction "SCL/SSZ_13") (pintype "bidirectional"))
    )
    (net (code "21") (name "/I2C_SDA") (class "Default")
      (node (ref "IC1") (pin "62") (pinfunction "PB9_62") (pintype "bidirectional"))
      (node (ref "R9") (pin "1") (pinfunction "1_1") (pintype "passive"))
      (node (ref "TP1") (pin "TP") (pinfunction "TP_TP") (pintype "input"))
      (node (ref "U4") (pin "3") (pinfunction "SDA_3") (pintype "input"))
      (node (ref "U5") (pin "24") (pinfunction "SDA/SDI_24") (pintype "bidirectional"))
      (node (ref "U9") (pin "14") (pinfunction "SDA/MOSI_14") (pintype "bidirectional"))
    )
    (net (code "22") (name "/KEY_1") (class "Default")
      (node (ref "IC1") (pin "56") (pinfunction "PB4_56") (pintype "bidirectional"))
      (node (ref "K1") (pin "SW1") (pinfunction "PIN-1_SW1") (pintype "bidirectional"))
      (node (ref "R22") (pin "1") (pinfunction "1_1") (pintype "passive"))
    )
    (net (code "23") (name "/KEY_2") (class "Default")
      (node (ref "IC1") (pin "27") (pinfunction "PB2_27") (pintype "bidirectional"))
      (node (ref "K2") (pin "SW1") (pinfunction "PIN-1_SW1") (pintype "bidirectional"))
      (node (ref "R23") (pin "1") (pinfunction "1_1") (pintype "passive"))
    )
    (net (code "24") (name "/KEY_3") (class "Default")
      (node (ref "IC1") (pin "2") (pinfunction "PC13_2") (pintype "bidirectional"))
      (node (ref "K3") (pin "1") (pinfunction "1_1") (pintype "passive"))
      (node (ref "K3") (pin "3") (pinfunction "1_3") (pintype "passive"))
      (node (ref "R24") (pin "1") (pinfunction "1_1") (pintype "passive"))
    )
    (net (code "25") (name "/KEY_4") (class "Default")
      (node (ref "IC1") (pin "3") (pinfunction "PC14_3") (pintype "bidirectional"))
      (node (ref "K4") (pin "1") (pinfunction "1_1") (pintype "passive"))
      (node (ref "K4") (pin "3") (pinfunction "1_3") (pintype "passive"))
      (node (ref "R25") (pin "1") (pinfunction "1_1") (pintype "passive"))
    )
    (net (code "26") (name "/KEY_5") (class "Default")
      (node (ref "IC1") (pin "4") (pinfunction "PC15_4") (pintype "bidirectional"))
      (node (ref "K5") (pin "1") (pinfunction "1_1") (pintype "passive"))
      (node (ref "K5") (pin "3") (pinfunction "1_3") (pintype "passive"))
      (node (ref "R26") (pin "1") (pinfunction "1_1") (pintype "passive"))
    )
    (net (code "27") (name "/LED_1") (class "Default")
      (node (ref "IC1") (pin "22") (pinfunction "PA6_22") (pintype "bidirectional"))
      (node (ref "Q3") (pin "1") (pinfunction "G_1") (pintype "passive"))
    )
    (net (code "28") (name "/LED_2") (class "Default")
      (node (ref "IC1") (pin "23") (pinfunction "PA7_23") (pintype "bidirectional"))
      (node (ref "Q4") (pin "1") (pinfunction "G_1") (pintype "passive"))
    )
    (net (code "29") (name "/LED_3") (class "Default")
      (node (ref "IC1") (pin "50") (pinfunction "PA15_50") (pintype "bidirectional"))
      (node (ref "Q5") (pin "1") (pinfunction "G_1") (pintype "passive"))
    )
    (net (code "30") (name "/LED_4") (class "Default")
      (node (ref "IC1") (pin "55") (pinfunction "PB3_55") (pintype "bidirectional"))
      (node (ref "Q6") (pin "1") (pinfunction "G_1") (pintype "passive"))
    )
    (net (code "31") (name "/LED_B") (class "Default")
      (node (ref "IC1") (pin "44") (pinfunction "PA11_44") (pintype "bidirectional"))
      (node (ref "R15") (pin "1") (pinfunction "1_1") (pintype "passive"))
    )
    (net (code "32") (name "/LED_G") (class "Default")
      (node (ref "IC1") (pin "43") (pinfunction "PA10_43") (pintype "bidirectional"))
      (node (ref "R14") (pin "1") (pinfunction "1_1") (pintype "passive"))
    )
    (net (code "33") (name "/LED_R") (class "Default")
      (node (ref "IC1") (pin "42") (pinfunction "PA9_42") (pintype "bidirectional"))
      (node (ref "R13") (pin "1") (pinfunction "1_1") (pintype "passive"))
    )
    (net (code "34") (name "/MCLK") (class "Default")
      (node (ref "IC1") (pin "41") (pinfunction "PA8_41") (pintype "bidirectional"))
      (node (ref "R21") (pin "1") (pinfunction "1_1") (pintype "passive"))
      (node (ref "U8") (pin "15") (pinfunction "REFCLK_15") (pintype "bidirectional"))
    )
    (net (code "35") (name "/MMC_CD") (class "Default")
      (node (ref "IC1") (pin "35") (pinfunction "PB14_35") (pintype "bidirectional"))
      (node (ref "J2") (pin "10") (pinfunction "CDSW2_10") (pintype "bidirectional"))
      (node (ref "J2") (pin "10-1") (pinfunction "CDSW2_10-1") (pintype "bidirectional"))
    )
    (net (code "36") (name "/MMC_CLK") (class "Default")
      (node (ref "IC1") (pin "53") (pinfunction "PC12_53") (pintype "bidirectional"))
      (node (ref "J2") (pin "5") (pinfunction "CLK_5") (pintype "bidirectional"))
    )
    (net (code "37") (name "/MMC_CMD") (class "Default")
      (node (ref "IC1") (pin "54") (pinfunction "PD2_54") (pintype "bidirectional"))
      (node (ref "J2") (pin "3") (pinfunction "CMD_3") (pintype "bidirectional"))
    )
    (net (code "38") (name "/MMC_D0") (class "Default")
      (node (ref "IC1") (pin "39") (pinfunction "PC8_39") (pintype "bidirectional"))
      (node (ref "J2") (pin "7") (pinfunction "DAT0_7") (pintype "bidirectional"))
    )
    (net (code "39") (name "/MMC_D1") (class "Default")
      (node (ref "IC1") (pin "40") (pinfunction "PC9_40") (pintype "bidirectional"))
      (node (ref "J2") (pin "8") (pinfunction "DAT1_8") (pintype "bidirectional"))
    )
    (net (code "40") (name "/MMC_D2") (class "Default")
      (node (ref "IC1") (pin "51") (pinfunction "PC10_51") (pintype "bidirectional"))
      (node (ref "J2") (pin "1") (pinfunction "DAT2_1") (pintype "bidirectional"))
    )
    (net (code "41") (name "/MMC_D3") (class "Default")
      (node (ref "IC1") (pin "52") (pinfunction "PC11_52") (pintype "bidirectional"))
      (node (ref "J2") (pin "2") (pinfunction "CD/DAT3_2") (pintype "bidirectional"))
    )
    (net (code "42") (name "/MPU_INT") (class "Default")
      (node (ref "IC1") (pin "58") (pinfunction "PB6_58") (pintype "bidirectional"))
      (node (ref "U5") (pin "12") (pinfunction "INT_12") (pintype "bidirectional"))
    )
    (net (code "43") (name "/NRST_N") (class "Default")
      (node (ref "U2") (pin "20") (pinfunction "ADBUS7_20") (pintype "bidirectional"))
    )
    (net (code "44") (name "/RGB_B") (class "Default")
      (node (ref "D2") (pin "1") (pinfunction "KB_1") (pintype "passive"))
      (node (ref "D3") (pin "1") (pinfunction "KB_1") (pintype "passive"))
      (node (ref "D4") (pin "B") (pinfunction "KB_B") (pintype "passive"))
      (node (ref "D5") (pin "B") (pinfunction "KB_B") (pintype "passive"))
      (node (ref "R15") (pin "2") (pinfunction "2_2") (pintype "passive"))
    )
    (net (code "45") (name "/RGB_G") (class "Default")
      (node (ref "D2") (pin "4") (pinfunction "KG_4") (pintype "passive"))
      (node (ref "D3") (pin "4") (pinfunction "KG_4") (pintype "passive"))
      (node (ref "D4") (pin "G") (pinfunction "KG_G") (pintype "passive"))
      (node (ref "D5") (pin "G") (pinfunction "KG_G") (pintype "passive"))
      (node (ref "R14") (pin "2") (pinfunction "2_2") (pintype "passive"))
    )
    (net (code "46") (name "/RGB_R") (class "Default")
      (node (ref "D2") (pin "3") (pinfunction "KR_3") (pintype "passive"))
      (node (ref "D3") (pin "3") (pinfunction "KR_3") (pintype "passive"))
      (node (ref "D4") (pin "R") (pinfunction "KR_R") (pintype "passive"))
      (node (ref "D5") (pin "R") (pinfunction "KR_R") (pintype "passive"))
      (node (ref "R13") (pin "2") (pinfunction "2_2") (pintype "passive"))
    )
    (net (code "47") (name "/SRST_N") (class "Default")
      (node (ref "C39") (pin "2") (pinfunction "2_2") (pintype "passive"))
      (node (ref "IC1") (pin "7") (pinfunction "NRST_7") (pintype "bidirectional"))
      (node (ref "R12") (pin "1") (pinfunction "1_1") (pintype "passive"))
      (node (ref "U2") (pin "19") (pinfunction "ADBUS6_19") (pintype "bidirectional"))
      (node (ref "U8") (pin "17") (pinfunction "RESETB_17") (pintype "bidirectional"))
      (node (ref "U9") (pin "3") (pinfunction "~{RESET}_3") (pintype "bidirectional"))
    )
    (net (code "48") (name "/SWCLK") (class "Default")
      (node (ref "IC1") (pin "49") (pinfunction "PA14_49") (pintype "bidirectional"))
      (node (ref "U2") (pin "12") (pinfunction "ADBUS0_12") (pintype "bidirectional"))
    )
    (net (code "49") (name "/SWDIO") (class "Default")
      (node (ref "IC1") (pin "46") (pinfunction "PA13_46") (pintype "bidirectional"))
      (node (ref "R6") (pin "1") (pinfunction "1_1") (pintype "passive"))
      (node (ref "U2") (pin "14") (pinfunction "ADBUS2_14") (pintype "bidirectional"))
    )
    (net (code "50") (name "/ULPI_CLK") (class "Default")
      (node (ref "IC1") (pin "21") (pinfunction "PA5_21") (pintype "bidirectional"))
      (node (ref "U8") (pin "27") (pinfunction "CLKOUT_27") (pintype "bidirectional"))
    )
    (net (code "51") (name "/ULPI_D0") (class "Default")
      (node (ref "IC1") (pin "17") (pinfunction "PA3_17") (pintype "bidirectional"))
      (node (ref "U8") (pin "1") (pinfunction "DATA0_1") (pintype "bidirectional"))
    )
    (net (code "52") (name "/ULPI_D1") (class "Default")
      (node (ref "IC1") (pin "25") (pinfunction "PB0_25") (pintype "bidirectional"))
      (node (ref "U8") (pin "32") (pinfunction "DATA1_32") (pintype "bidirectional"))
    )
    (net (code "53") (name "/ULPI_D2") (class "Default")
      (node (ref "IC1") (pin "26") (pinfunction "PB1_26") (pintype "bidirectional"))
      (node (ref "U8") (pin "31") (pinfunction "DATA2_31") (pintype "bidirectional"))
    )
    (net (code "54") (name "/ULPI_D3") (class "Default")
      (node (ref "IC1") (pin "28") (pinfunction "PB10_28") (pintype "bidirectional"))
      (node (ref "U8") (pin "28") (pinfunction "DATA3_28") (pintype "bidirectional"))
    )
    (net (code "55") (name "/ULPI_D4") (class "Default")
      (node (ref "IC1") (pin "29") (pinfunction "PB11_29") (pintype "bidirectional"))
      (node (ref "U8") (pin "26") (pinfunction "DATA4_26") (pintype "bidirectional"))
    )
    (net (code "56") (name "/ULPI_D5") (class "Default")
      (node (ref "IC1") (pin "33") (pinfunction "PB12_33") (pintype "bidirectional"))
      (node (ref "U8") (pin "25") (pinfunction "DATA5_25") (pintype "bidirectional"))
    )
    (net (code "57") (name "/ULPI_D6") (class "Default")
      (node (ref "IC1") (pin "34") (pinfunction "PB13_34") (pintype "bidirectional"))
      (node (ref "U8") (pin "24") (pinfunction "DATA6_24") (pintype "bidirectional"))
    )
    (net (code "58") (name "/ULPI_D7") (class "Default")
      (node (ref "IC1") (pin "57") (pinfunction "PB5_57") (pintype "bidirectional"))
      (node (ref "U8") (pin "23") (pinfunction "DATA7_23") (pintype "bidirectional"))
    )
    (net (code "59") (name "/ULPI_DIR") (class "Default")
      (node (ref "IC1") (pin "10") (pinfunction "PC2_10") (pintype "bidirectional"))
      (node (ref "U8") (pin "19") (pinfunction "DIR_19") (pintype "bidirectional"))
    )
    (net (code "60") (name "/ULPI_NXT") (class "Default")
      (node (ref "IC1") (pin "11") (pinfunction "PC3_11") (pintype "bidirectional"))
      (node (ref "U8") (pin "21") (pinfunction "NXT_21") (pintype "bidirectional"))
    )
    (net (code "61") (name "/ULPI_STP") (class "Default")
      (node (ref "IC1") (pin "8") (pinfunction "PC0_8") (pintype "bidirectional"))
      (node (ref "U8") (pin "20") (pinfunction "STP_20") (pintype "bidirectional"))
    )
    (net (code "62") (name "AGND") (class "Default")
      (node (ref "C38") (pin "1") (pinfunction "1_1") (pintype "passive"))
      (node (ref "C41") (pin "2") (pinfunction "2_2") (pintype "passive"))
      (node (ref "C43") (pin "1") (pinfunction "1_1") (pintype "passive"))
      (node (ref "C44") (pin "1") (pinfunction "1_1") (pintype "passive"))
      (node (ref "C50") (pin "2") (pinfunction "2_2") (pintype "passive"))
      (node (ref "C53") (pin "2") (pinfunction "2_2") (pintype "passive"))
      (node (ref "C54") (pin "2") (pinfunction "2_2") (pintype "passive"))
      (node (ref "J4") (pin "4") (pinfunction "4_4") (pintype "bidirectional"))
      (node (ref "R11") (pin "2") (pinfunction "2_2") (pintype "passive"))
      (node (ref "R30") (pin "2") (pinfunction "2_2") (pintype "passive"))
      (node (ref "U9") (pin "21") (pinfunction "AVSS_21") (pintype "bidirectional"))
      (node (ref "U9") (pin "41") (pinfunction "PAD_41") (pintype "bidirectional"))
    )
    (net (code "63") (name "GND") (class "Default")
      (node (ref "C1") (pin "1") (pinfunction "1_1") (pintype "passive"))
      (node (ref "C10") (pin "1") (pinfunction "1_1") (pintype "passive"))
      (node (ref "C11") (pin "1") (pinfunction "1_1") (pintype "passive"))
      (node (ref "C12") (pin "1") (pinfunction "1_1") (pintype "passive"))
      (node (ref "C13") (pin "1") (pinfunction "1_1") (pintype "passive"))
      (node (ref "C14") (pin "1") (pinfunction "1_1") (pintype "passive"))
      (node (ref "C15") (pin "1") (pinfunction "1_1") (pintype "passive"))
      (node (ref "C16") (pin "1") (pinfunction "1_1") (pintype "passive"))
      (node (ref "C17") (pin "1") (pinfunction "1_1") (pintype "passive"))
      (node (ref "C18") (pin "1") (pinfunction "1_1") (pintype "passive"))
      (node (ref "C19") (pin "1") (pinfunction "1_1") (pintype "passive"))
      (node (ref "C2") (pin "1") (pinfunction "1_1") (pintype "passive"))
      (node (ref "C20") (pin "1") (pinfunction "1_1") (pintype "passive"))
      (node (ref "C21") (pin "1") (pinfunction "1_1") (pintype "passive"))
      (node (ref "C22") (pin "1") (pinfunction "1_1") (pintype "passive"))
      (node (ref "C23") (pin "1") (pinfunction "1_1") (pintype "passive"))
      (node (ref "C24") (pin "1") (pinfunction "1_1") (pintype "passive"))
      (node (ref "C25") (pin "1") (pinfunction "1_1") (pintype "passive"))
      (node (ref "C26") (pin "1") (pinfunction "1_1") (pintype "passive"))
      (node (ref "C27") (pin "1") (pinfunction "1_1") (pintype "passive"))
      (node (ref "C28") (pin "1") (pinfunction "1_1") (pintype "passive"))
      (node (ref "C29") (pin "1") (pinfunction "1_1") (pintype "passive"))
      (node (ref "C3") (pin "2") (pinfunction "2_2") (pintype "passive"))
      (node (ref "C30") (pin "1") (pinfunction "1_1") (pintype "passive"))
      (node (ref "C31") (pin "1") (pinfunction "1_1") (pintype "passive"))
      (node (ref "C32") (pin "1") (pinfunction "1_1") (pintype "passive"))
      (node (ref "C33") (pin "1") (pinfunction "1_1") (pintype "passive"))
      (node (ref "C34") (pin "1") (pinfunction "1_1") (pintype "passive"))
      (node (ref "C35") (pin "1") (pinfunction "1_1") (pintype "passive"))
      (node (ref "C36") (pin "1") (pinfunction "1_1") (pintype "passive"))
      (node (ref "C37") (pin "1") (pinfunction "1_1") (pintype "passive"))
      (node (ref "C39") (pin "1") (pinfunction "1_1") (pintype "passive"))
      (node (ref "C4") (pin "1") (pinfunction "1_1") (pintype "passive"))
      (node (ref "C40") (pin "1") (pinfunction "1_1") (pintype "passive"))
      (node (ref "C42") (pin "1") (pinfunction "1_1") (pintype "passive"))
      (node (ref "C45") (pin "1") (pinfunction "1_1") (pintype "passive"))
      (node (ref "C46") (pin "1") (pinfunction "1_1") (pintype "passive"))
      (node (ref "C47") (pin "1") (pinfunction "1_1") (pintype "passive"))
      (node (ref "C49") (pin "1") (pinfunction "1_1") (pintype "passive"))
      (node (ref "C5") (pin "1") (pinfunction "1_1") (pintype "passive"))
      (node (ref "C52") (pin "1") (pinfunction "1_1") (pintype "passive"))
      (node (ref "C55") (pin "2") (pinfunction "2_2") (pintype "passive"))
      (node (ref "C6") (pin "1") (pinfunction "1_1") (pintype "passive"))
      (node (ref "C7") (pin "1") (pinfunction "1_1") (pintype "passive"))
      (node (ref "C8") (pin "1") (pinfunction "1_1") (pintype "passive"))
      (node (ref "C9") (pin "1") (pinfunction "1_1") (pintype "passive"))
      (node (ref "IC1") (pin "12") (pinfunction "VSSA_12") (pintype "power_in"))
      (node (ref "IC1") (pin "18") (pinfunction "VSS_18") (pintype "power_in"))
      (node (ref "IC1") (pin "31") (pinfunction "VSS_31") (pintype "power_in"))
      (node (ref "IC1") (pin "47") (pinfunction "VSS_47") (pintype "power_in"))
      (node (ref "IC1") (pin "63") (pinfunction "VSS_63") (pintype "power_in"))
      (node (ref "J1") (pin "5") (pinfunction "5GND_5") (pintype "passive"))
      (node (ref "J1") (pin "Z1") (pinfunction "GND_Z1") (pintype "bidirectional"))
      (node (ref "J1") (pin "Z2") (pinfunction "GND_Z2") (pintype "bidirectional"))
      (node (ref "J1") (pin "Z3") (pinfunction "GND_Z3") (pintype "bidirectional"))
      (node (ref "J1") (pin "Z4") (pinfunction "GND_Z4") (pintype "bidirectional"))
      (node (ref "J2") (pin "6") (pinfunction "VSS_6") (pintype "bidirectional"))
      (node (ref "J2") (pin "9") (pinfunction "CDSW1_9") (pintype "bidirectional"))
      (node (ref "J2") (pin "9-1") (pinfunction "CDSW1_9-1") (pintype "bidirectional"))
      (node (ref "J3") (pin "A1") (pinfunction "GND_A1") (pintype "passive"))
      (node (ref "J3") (pin "A12") (pinfunction "GND_A12") (pintype "passive"))
      (node (ref "J3") (pin "B1") (pinfunction "GND_B1") (pintype "passive"))
      (node (ref "J3") (pin "B12") (pinfunction "GND_B12") (pintype "passive"))
      (node (ref "J3") (pin "Z1") (pinfunction "SHIELD_Z1") (pintype "passive"))
      (node (ref "J3") (pin "Z2") (pinfunction "SHIELD_Z2") (pintype "passive"))
      (node (ref "J3") (pin "Z3") (pinfunction "SHIELD_Z3") (pintype "passive"))
      (node (ref "J3") (pin "Z4") (pinfunction "SHIELD_Z4") (pintype "passive"))
      (node (ref "K1") (pin "SW2") (pinfunction "PIN-2_SW2") (pintype "bidirectional"))
      (node (ref "K2") (pin "SW2") (pinfunction "PIN-2_SW2") (pintype "bidirectional"))
      (node (ref "K3") (pin "2") (pinfunction "2_2") (pintype "passive"))
      (node (ref "K3") (pin "4") (pinfunction "2_4") (pintype "passive"))
      (node (ref "K4") (pin "2") (pinfunction "2_2") (pintype "passive"))
      (node (ref "K4") (pin "4") (pinfunction "2_4") (pintype "passive"))
      (node (ref "K5") (pin "2") (pinfunction "2_2") (pintype "passive"))
      (node (ref "K5") (pin "4") (pinfunction "2_4") (pintype "passive"))
      (node (ref "R10") (pin "2") (pinfunction "2_2") (pintype "passive"))
      (node (ref "R11") (pin "1") (pinfunction "1_1") (pintype "passive"))
      (node (ref "R27") (pin "1") (pinfunction "1_1") (pintype "passive"))
      (node (ref "R31") (pin "1") (pinfunction "1_1") (pintype "passive"))
      (node (ref "R32") (pin "1") (pinfunction "1_1") (pintype "passive"))
      (node (ref "R4") (pin "2") (pinfunction "2_2") (pintype "passive"))
      (node (ref "TP4") (pin "TP") (pinfunction "TP_TP") (pintype "input"))
      (node (ref "TP9") (pin "TP") (pinfunction "TP_TP") (pintype "input"))
      (node (ref "U1") (pin "2") (pinfunction "GND_2") (pintype "input"))
      (node (ref "U2") (pin "10") (pinfunction "TEST_10") (pintype "input"))
      (node (ref "U2") (pin "21") (pinfunction "GND_21") (pintype "power_in"))
      (node (ref "U2") (pin "41") (pinfunction "GND_41") (pintype "power_in"))
      (node (ref "U2") (pin "45") (pinfunction "GND_45") (pintype "power_in"))
      (node (ref "U2") (pin "57") (pinfunction "EXP_57") (pintype "power_in"))
      (node (ref "U3") (pin "2") (pinfunction "GND_2") (pintype "input"))
      (node (ref "U4") (pin "2") (pinfunction "VSS_2") (pintype "power_in"))
      (node (ref "U5") (pin "18") (pinfunction "GND_18") (pintype "bidirectional"))
      (node (ref "U5") (pin "20") (pinfunction "GND_20") (pintype "bidirectional"))
      (node (ref "U5") (pin "9") (pinfunction "AD0/SDO_9") (pintype "bidirectional"))
      (node (ref "U6") (pin "2") (pinfunction "GND_2") (pintype "input"))
      (node (ref "U7") (pin "2") (pinfunction "GND_2") (pintype "input"))
      (node (ref "U8") (pin "8") (pinfunction "GND_8") (pintype "bidirectional"))
      (node (ref "U8") (pin "EXP") (pinfunction "GND_EXP") (pintype "bidirectional"))
      (node (ref "U9") (pin "1") (pinfunction "DVSS_1") (pintype "bidirectional"))
      (node (ref "U9") (pin "11") (pinfunction "IOVSS_11") (pintype "bidirectional"))
      (node (ref "U9") (pin "16") (pinfunction "SPI_SELECT_16") (pintype "bidirectional"))
      (node (ref "U9") (pin "2") (pinfunction "DVSS_2") (pintype "bidirectional"))
      (node (ref "U9") (pin "37") (pinfunction "DVSS_CP_37") (pintype "bidirectional"))
    )
    (net (code "64") (name "Net-(D1-KB)") (class "Default")
      (node (ref "D1") (pin "B") (pinfunction "KB_B") (pintype "passive"))
      (node (ref "R3") (pin "2") (pinfunction "2_2") (pintype "passive"))
    )
    (net (code "65") (name "Net-(D1-KG)") (class "Default")
      (node (ref "D1") (pin "G") (pinfunction "KG_G") (pintype "passive"))
      (node (ref "R2") (pin "2") (pinfunction "2_2") (pintype "passive"))
    )
    (net (code "66") (name "Net-(D1-KR)") (class "Default")
      (node (ref "D1") (pin "R") (pinfunction "KR_R") (pintype "passive"))
      (node (ref "R1") (pin "2") (pinfunction "2_2") (pintype "passive"))
    )
    (net (code "67") (name "Net-(D2-A)") (class "Default")
      (node (ref "D2") (pin "2") (pinfunction "A_2") (pintype "bidirectional"))
      (node (ref "Q3") (pin "2") (pinfunction "D_2") (pintype "passive"))
    )
    (net (code "68") (name "Net-(D3-A)") (class "Default")
      (node (ref "D3") (pin "2") (pinfunction "A_2") (pintype "bidirectional"))
      (node (ref "Q4") (pin "2") (pinfunction "D_2") (pintype "passive"))
    )
    (net (code "69") (name "Net-(D4-A)") (class "Default")
      (node (ref "D4") (pin "CA") (pinfunction "A_CA") (pintype "bidirectional"))
      (node (ref "Q5") (pin "2") (pinfunction "D_2") (pintype "passive"))
    )
    (net (code "70") (name "Net-(D5-A)") (class "Default")
      (node (ref "D5") (pin "CA") (pinfunction "A_CA") (pintype "bidirectional"))
      (node (ref "Q6") (pin "2") (pinfunction "D_2") (pintype "passive"))
    )
    (net (code "71") (name "Net-(IC1A-OSC_IN)") (class "Default")
      (node (ref "C28") (pin "2") (pinfunction "2_2") (pintype "passive"))
      (node (ref "IC1") (pin "5") (pinfunction "OSC_IN_5") (pintype "bidirectional"))
      (node (ref "Q2") (pin "1") (pinfunction "1_1") (pintype "passive"))
    )
    (net (code "72") (name "Net-(IC1A-OSC_OUT)") (class "Default")
      (node (ref "C31") (pin "2") (pinfunction "2_2") (pintype "passive"))
      (node (ref "IC1") (pin "6") (pinfunction "OSC_OUT_6") (pintype "bidirectional"))
      (node (ref "Q2") (pin "3") (pinfunction "2_3") (pintype "passive"))
    )
    (net (code "73") (name "Net-(IC1A-VCAP1)") (class "Default")
      (node (ref "C40") (pin "2") (pinfunction "2_2") (pintype "passive"))
      (node (ref "IC1") (pin "30") (pinfunction "VCAP1_30") (pintype "power_in"))
    )
    (net (code "74") (name "Net-(J1-1VCC)") (class "Default")
      (node (ref "C25") (pin "2") (pinfunction "2_2") (pintype "passive"))
      (node (ref "C26") (pin "2") (pinfunction "2_2") (pintype "passive"))
      (node (ref "J1") (pin "1") (pinfunction "1VCC_1") (pintype "passive"))
      (node (ref "U6") (pin "1") (pinfunction "IN_1") (pintype "input"))
      (node (ref "U6") (pin "3") (pinfunction "EN_3") (pintype "input"))
    )
    (net (code "75") (name "Net-(J1-2D-)") (class "Default")
      (node (ref "J1") (pin "2") (pinfunction "2D-_2") (pintype "passive"))
      (node (ref "U2") (pin "7") (pinfunction "DM_7") (pintype "bidirectional"))
    )
    (net (code "76") (name "Net-(J1-3D+)") (class "Default")
      (node (ref "J1") (pin "3") (pinfunction "3D+_3") (pintype "passive"))
      (node (ref "U2") (pin "8") (pinfunction "DP_8") (pintype "bidirectional"))
    )
    (net (code "77") (name "Net-(J3-CC1)") (class "Default")
      (node (ref "J3") (pin "A5") (pinfunction "CC1_A5") (pintype "passive"))
      (node (ref "R32") (pin "2") (pinfunction "2_2") (pintype "passive"))
    )
    (net (code "78") (name "Net-(J3-CC2)") (class "Default")
      (node (ref "J3") (pin "B5") (pinfunction "CC2_B5") (pintype "passive"))
      (node (ref "R31") (pin "2") (pinfunction "2_2") (pintype "passive"))
    )
    (net (code "79") (name "Net-(Q1-1)") (class "Default")
      (node (ref "C7") (pin "2") (pinfunction "2_2") (pintype "passive"))
      (node (ref "Q1") (pin "P$1") (pinfunction "1_P$1") (pintype "passive"))
      (node (ref "U2") (pin "4") (pinfunction "OSCO_4") (pintype "output"))
    )
    (net (code "80") (name "Net-(Q1-2)") (class "Default")
      (node (ref "C9") (pin "2") (pinfunction "2_2") (pintype "passive"))
      (node (ref "Q1") (pin "P$3") (pinfunction "2_P$3") (pintype "passive"))
      (node (ref "U2") (pin "3") (pinfunction "OSCI_3") (pintype "input"))
    )
    (net (code "81") (name "Net-(U2-ADBUS1)") (class "Default")
      (node (ref "R6") (pin "2") (pinfunction "2_2") (pintype "passive"))
      (node (ref "U2") (pin "13") (pinfunction "ADBUS1_13") (pintype "bidirectional"))
    )
    (net (code "82") (name "Net-(U2-EEDATA)") (class "Default")
      (node (ref "R7") (pin "1") (pinfunction "1_1") (pintype "passive"))
      (node (ref "U2") (pin "55") (pinfunction "EEDATA_55") (pintype "bidirectional"))
    )
    (net (code "83") (name "Net-(U2-REF)") (class "Default")
      (node (ref "R4") (pin "1") (pinfunction "1_1") (pintype "passive"))
      (node (ref "U2") (pin "6") (pinfunction "REF_6") (pintype "input"))
    )
    (net (code "84") (name "Net-(U2-VPHY)") (class "Default")
      (node (ref "C16") (pin "2") (pinfunction "2_2") (pintype "passive"))
      (node (ref "C18") (pin "2") (pinfunction "2_2") (pintype "passive"))
      (node (ref "L1") (pin "1") (pinfunction "1_1") (pintype "passive"))
      (node (ref "U2") (pin "5") (pinfunction "VPHY_5") (pintype "power_in"))
    )
    (net (code "85") (name "Net-(U2-VPLL)") (class "Default")
      (node (ref "C21") (pin "2") (pinfunction "2_2") (pintype "passive"))
      (node (ref "C22") (pin "2") (pinfunction "2_2") (pintype "passive"))
      (node (ref "L2") (pin "1") (pinfunction "1_1") (pintype "passive"))
      (node (ref "U2") (pin "9") (pinfunction "VPLL_9") (pintype "power_in"))
    )
    (net (code "86") (name "Net-(U2-~{RESET#})") (class "Default")
      (node (ref "R5") (pin "1") (pinfunction "1_1") (pintype "passive"))
      (node (ref "U2") (pin "11") (pinfunction "~{RESET#}_11") (pintype "input"))
    )
    (net (code "87") (name "Net-(U5-REGOUT)") (class "Default")
      (node (ref "C20") (pin "2") (pinfunction "2_2") (pintype "passive"))
      (node (ref "U5") (pin "10") (pinfunction "REGOUT_10") (pintype "bidirectional"))
    )
    (net (code "88") (name "Net-(U8-DM)") (class "Default")
      (node (ref "J3") (pin "A7") (pinfunction "D-_A7") (pintype "passive"))
      (node (ref "J3") (pin "B7") (pinfunction "D-_B7") (pintype "passive"))
      (node (ref "U8") (pin "4") (pinfunction "DM_4") (pintype "bidirectional"))
    )
    (net (code "89") (name "Net-(U8-DP)") (class "Default")
      (node (ref "J3") (pin "A6") (pinfunction "D+_A6") (pintype "passive"))
      (node (ref "J3") (pin "B6") (pinfunction "D+_B6") (pintype "passive"))
      (node (ref "U8") (pin "5") (pinfunction "DP_5") (pintype "bidirectional"))
    )
    (net (code "90") (name "Net-(U8-RBIAS)") (class "Default")
      (node (ref "R27") (pin "2") (pinfunction "2_2") (pintype "passive"))
      (node (ref "U8") (pin "3") (pinfunction "RBIAS_3") (pintype "bidirectional"))
    )
    (net (code "91") (name "Net-(U8-VBUS)") (class "Default")
      (node (ref "R28") (pin "1") (pinfunction "1_1") (pintype "passive"))
      (node (ref "U8") (pin "13") (pinfunction "VBUS_13") (pintype "bidirectional"))
    )
    (net (code "92") (name "Net-(U8-VDD18)") (class "Default")
      (node (ref "C46") (pin "2") (pinfunction "2_2") (pintype "passive"))
      (node (ref "U8") (pin "18") (pinfunction "VDD18_18") (pintype "bidirectional"))
    )
    (net (code "93") (name "Net-(U8-VDD33)") (class "Default")
      (node (ref "C45") (pin "2") (pinfunction "2_2") (pintype "passive"))
      (node (ref "U8") (pin "14") (pinfunction "VDD33_14") (pintype "bidirectional"))
      (node (ref "U8") (pin "2") (pinfunction "VDDIO_2") (pintype "bidirectional"))
      (node (ref "U8") (pin "22") (pinfunction "VDDIO_22") (pintype "bidirectional"))
      (node (ref "U8") (pin "30") (pinfunction "VDDIO_30") (pintype "bidirectional"))
    )
    (net (code "94") (name "Net-(U9-BCLK)") (class "Default")
      (node (ref "R18") (pin "2") (pinfunction "2_2") (pintype "passive"))
      (node (ref "U9") (pin "6") (pinfunction "BCLK_6") (pintype "bidirectional"))
    )
    (net (code "95") (name "Net-(U9-DIN{slash}MFP1)") (class "Default")
      (node (ref "R17") (pin "2") (pinfunction "2_2") (pintype "passive"))
      (node (ref "U9") (pin "8") (pinfunction "DIN/MFP1_8") (pintype "bidirectional"))
    )
    (net (code "96") (name "Net-(U9-DOUT{slash}MFP2)") (class "Default")
      (node (ref "R19") (pin "2") (pinfunction "2_2") (pintype "passive"))
      (node (ref "U9") (pin "9") (pinfunction "DOUT/MFP2_9") (pintype "bidirectional"))
    )
    (net (code "97") (name "Net-(U9-FLY_N)") (class "Default")
      (node (ref "C48") (pin "1") (pinfunction "1_1") (pintype "passive"))
      (node (ref "U9") (pin "36") (pinfunction "FLY_N_36") (pintype "bidirectional"))
    )
    (net (code "98") (name "Net-(U9-FLY_P)") (class "Default")
      (node (ref "C48") (pin "2") (pinfunction "2_2") (pintype "passive"))
      (node (ref "U9") (pin "38") (pinfunction "FLY_P_38") (pintype "bidirectional"))
    )
    (net (code "99") (name "Net-(U9-GND_SENSE)") (class "Default")
      (node (ref "R30") (pin "1") (pinfunction "1_1") (pintype "passive"))
      (node (ref "U9") (pin "28") (pinfunction "GND_SENSE_28") (pintype "bidirectional"))
    )
    (net (code "100") (name "Net-(U9-GPIO{slash}MFP5)") (class "Default")
      (node (ref "R16") (pin "2") (pinfunction "2_2") (pintype "passive"))
      (node (ref "U9") (pin "4") (pinfunction "GPIO/MFP5_4") (pintype "bidirectional"))
    )
    (net (code "101") (name "Net-(U9-HPL)") (class "Default")
      (node (ref "J4") (pin "2") (pinfunction "2_2") (pintype "bidirectional"))
      (node (ref "U9") (pin "31") (pinfunction "HPL_31") (pintype "bidirectional"))
    )
    (net (code "102") (name "Net-(U9-HPR)") (class "Default")
      (node (ref "J4") (pin "3") (pinfunction "3_3") (pintype "bidirectional"))
      (node (ref "U9") (pin "33") (pinfunction "HPR_33") (pintype "bidirectional"))
    )
    (net (code "103") (name "Net-(U9-IN1_L)") (class "Default")
      (node (ref "C53") (pin "1") (pinfunction "1_1") (pintype "passive"))
      (node (ref "U9") (pin "17") (pinfunction "IN1_L_17") (pintype "bidirectional"))
      (node (ref "U9") (pin "18") (pinfunction "IN1_R_18") (pintype "bidirectional"))
      (node (ref "U9") (pin "19") (pinfunction "IN2_L_19") (pintype "bidirectional"))
      (node (ref "U9") (pin "20") (pinfunction "IN2_R_20") (pintype "bidirectional"))
      (node (ref "U9") (pin "25") (pinfunction "IN3_R_25") (pintype "bidirectional"))
    )
    (net (code "104") (name "Net-(U9-IN3_L)") (class "Default")
      (node (ref "C51") (pin "1") (pinfunction "1_1") (pintype "passive"))
      (node (ref "U9") (pin "24") (pinfunction "IN3_L_24") (pintype "bidirectional"))
    )
    (net (code "105") (name "Net-(U9-MCLK)") (class "Default")
      (node (ref "R21") (pin "2") (pinfunction "2_2") (pintype "passive"))
      (node (ref "U9") (pin "5") (pinfunction "MCLK_5") (pintype "bidirectional"))
    )
    (net (code "106") (name "Net-(U9-MICBIAS)") (class "Default")
      (node (ref "R29") (pin "1") (pinfunction "1_1") (pintype "passive"))
      (node (ref "U9") (pin "23") (pinfunction "MICBIAS_23") (pintype "bidirectional"))
    )
    (net (code "107") (name "Net-(U9-MICDET)") (class "Default")
      (node (ref "C51") (pin "2") (pinfunction "2_2") (pintype "passive"))
      (node (ref "J4") (pin "1") (pinfunction "1_1") (pintype "bidirectional"))
      (node (ref "R29") (pin "2") (pinfunction "2_2") (pintype "passive"))
      (node (ref "U9") (pin "34") (pinfunction "MICDET_34") (pintype "bidirectional"))
    )
    (net (code "108") (name "Net-(U9-REF)") (class "Default")
      (node (ref "C50") (pin "1") (pinfunction "1_1") (pintype "passive"))
      (node (ref "U9") (pin "22") (pinfunction "REF_22") (pintype "bidirectional"))
    )
    (net (code "109") (name "Net-(U9-VNEG)") (class "Default")
      (node (ref "C41") (pin "1") (pinfunction "1_1") (pintype "passive"))
      (node (ref "U9") (pin "35") (pinfunction "VNEG_35") (pintype "bidirectional"))
    )
    (net (code "110") (name "Net-(U9-WCLK)") (class "Default")
      (node (ref "R20") (pin "2") (pinfunction "2_2") (pintype "passive"))
      (node (ref "U9") (pin "7") (pinfunction "WCLK_7") (pintype "bidirectional"))
    )
    (net (code "111") (name "V+") (class "Default")
      (node (ref "C38") (pin "2") (pinfunction "2_2") (pintype "passive"))
      (node (ref "C43") (pin "2") (pinfunction "2_2") (pintype "passive"))
      (node (ref "C54") (pin "1") (pinfunction "1_1") (pintype "passive"))
      (node (ref "U7") (pin "5") (pinfunction "OUT_5") (pintype "passive"))
      (node (ref "U9") (pin "29") (pinfunction "AVDD_29") (pintype "bidirectional"))
      (node (ref "U9") (pin "32") (pinfunction "DRVDD_HP_32") (pintype "bidirectional"))
    )
    (net (code "112") (name "unconnected-(IC1A-PB15-Pad36)") (class "Default")
      (node (ref "IC1") (pin "36") (pinfunction "PB15_36") (pintype "bidirectional"))
    )
    (net (code "113") (name "unconnected-(J1-4ID-Pad4)") (class "Default")
      (node (ref "J1") (pin "4") (pinfunction "4ID_4") (pintype "passive"))
    )
    (net (code "114") (name "unconnected-(J4-Pad5)") (class "Default")
      (node (ref "J4") (pin "5") (pinfunction "5_5") (pintype "bidirectional"))
    )
    (net (code "115") (name "unconnected-(U1-NC-Pad4)") (class "Default")
      (node (ref "U1") (pin "4") (pinfunction "NC_4") (pintype "no_connect"))
    )
    (net (code "116") (name "unconnected-(U2-ACBUS0-Pad22)") (class "Default")
      (node (ref "U2") (pin "22") (pinfunction "ACBUS0_22") (pintype "bidirectional"))
    )
    (net (code "117") (name "unconnected-(U2-ACBUS1-Pad23)") (class "Default")
      (node (ref "U2") (pin "23") (pinfunction "ACBUS1_23") (pintype "bidirectional"))
    )
    (net (code "118") (name "unconnected-(U2-ACBUS3-Pad25)") (class "Default")
      (node (ref "U2") (pin "25") (pinfunction "ACBUS3_25") (pintype "bidirectional"))
    )
    (net (code "119") (name "unconnected-(U2-ACBUS4-Pad26)") (class "Default")
      (node (ref "U2") (pin "26") (pinfunction "ACBUS4_26") (pintype "bidirectional"))
    )
    (net (code "120") (name "unconnected-(U2-ACBUS5-Pad27)") (class "Default")
      (node (ref "U2") (pin "27") (pinfunction "ACBUS5_27") (pintype "bidirectional"))
    )
    (net (code "121") (name "unconnected-(U2-ACBUS6-Pad28)") (class "Default")
      (node (ref "U2") (pin "28") (pinfunction "ACBUS6_28") (pintype "bidirectional"))
    )
    (net (code "122") (name "unconnected-(U2-ACBUS7-Pad29)") (class "Default")
      (node (ref "U2") (pin "29") (pinfunction "ACBUS7_29") (pintype "bidirectional"))
    )
    (net (code "123") (name "unconnected-(U2-ADBUS3-Pad15)") (class "Default")
      (node (ref "U2") (pin "15") (pinfunction "ADBUS3_15") (pintype "bidirectional"))
    )
    (net (code "124") (name "unconnected-(U2-ADBUS4-Pad17)") (class "Default")
      (node (ref "U2") (pin "17") (pinfunction "ADBUS4_17") (pintype "bidirectional"))
    )
    (net (code "125") (name "unconnected-(U2-ADBUS5-Pad18)") (class "Default")
      (node (ref "U2") (pin "18") (pinfunction "ADBUS5_18") (pintype "bidirectional"))
    )
    (net (code "126") (name "unconnected-(U2-BCBUS0-Pad42)") (class "Default")
      (node (ref "U2") (pin "42") (pinfunction "BCBUS0_42") (pintype "bidirectional"))
    )
    (net (code "127") (name "unconnected-(U2-BCBUS1-Pad46)") (class "Default")
      (node (ref "U2") (pin "46") (pinfunction "BCBUS1_46") (pintype "bidirectional"))
    )
    (net (code "128") (name "unconnected-(U2-BCBUS2-Pad47)") (class "Default")
      (node (ref "U2") (pin "47") (pinfunction "BCBUS2_47") (pintype "bidirectional"))
    )
    (net (code "129") (name "unconnected-(U2-BCBUS5-Pad51)") (class "Default")
      (node (ref "U2") (pin "51") (pinfunction "BCBUS5_51") (pintype "bidirectional"))
    )
    (net (code "130") (name "unconnected-(U2-BCBUS6-Pad52)") (class "Default")
      (node (ref "U2") (pin "52") (pinfunction "BCBUS6_52") (pintype "bidirectional"))
    )
    (net (code "131") (name "unconnected-(U2-BCBUS7-Pad53)") (class "Default")
      (node (ref "U2") (pin "53") (pinfunction "BCBUS7_53") (pintype "bidirectional"))
    )
    (net (code "132") (name "unconnected-(U2-BDBUS2-Pad34)") (class "Default")
      (node (ref "U2") (pin "34") (pinfunction "BDBUS2_34") (pintype "bidirectional"))
    )
    (net (code "133") (name "unconnected-(U2-BDBUS3-Pad35)") (class "Default")
      (node (ref "U2") (pin "35") (pinfunction "BDBUS3_35") (pintype "bidirectional"))
    )
    (net (code "134") (name "unconnected-(U2-BDBUS4-Pad37)") (class "Default")
      (node (ref "U2") (pin "37") (pinfunction "BDBUS4_37") (pintype "bidirectional"))
    )
    (net (code "135") (name "unconnected-(U2-BDBUS5-Pad38)") (class "Default")
      (node (ref "U2") (pin "38") (pinfunction "BDBUS5_38") (pintype "bidirectional"))
    )
    (net (code "136") (name "unconnected-(U2-BDBUS6-Pad39)") (class "Default")
      (node (ref "U2") (pin "39") (pinfunction "BDBUS6_39") (pintype "bidirectional"))
    )
    (net (code "137") (name "unconnected-(U2-BDBUS7-Pad40)") (class "Default")
      (node (ref "U2") (pin "40") (pinfunction "BDBUS7_40") (pintype "bidirectional"))
    )
    (net (code "138") (name "unconnected-(U2-EECLK-Pad56)") (class "Default")
      (node (ref "U2") (pin "56") (pinfunction "EECLK_56") (pintype "output"))
    )
    (net (code "139") (name "unconnected-(U2-EECS-Pad1)") (class "Default")
      (node (ref "U2") (pin "1") (pinfunction "EECS_1") (pintype "bidirectional"))
    )
    (net (code "140") (name "unconnected-(U2-~{PWREN#}-Pad54)") (class "Default")
      (node (ref "U2") (pin "54") (pinfunction "~{PWREN#}_54") (pintype "output"))
    )
    (net (code "141") (name "unconnected-(U2-~{SUSPEND#}-Pad30)") (class "Default")
      (node (ref "U2") (pin "30") (pinfunction "~{SUSPEND#}_30") (pintype "output"))
    )
    (net (code "142") (name "unconnected-(U3-NC-Pad4)") (class "Default")
      (node (ref "U3") (pin "4") (pinfunction "NC_4") (pintype "no_connect"))
    )
    (net (code "143") (name "unconnected-(U4-NC-Pad5)") (class "Default")
      (node (ref "U4") (pin "5") (pinfunction "NC_5") (pintype "bidirectional"))
    )
    (net (code "144") (name "unconnected-(U5-AUX_CL-Pad7)") (class "Default")
      (node (ref "U5") (pin "7") (pinfunction "AUX_CL_7") (pintype "bidirectional"))
    )
    (net (code "145") (name "unconnected-(U5-AUX_DA-Pad21)") (class "Default")
      (node (ref "U5") (pin "21") (pinfunction "AUX_DA_21") (pintype "bidirectional"))
    )
    (net (code "146") (name "unconnected-(U5-FSYNC-Pad11)") (class "Default")
      (node (ref "U5") (pin "11") (pinfunction "FSYNC_11") (pintype "bidirectional"))
    )
    (net (code "147") (name "unconnected-(U6-NC-Pad4)") (class "Default")
      (node (ref "U6") (pin "4") (pinfunction "NC_4") (pintype "no_connect"))
    )
    (net (code "148") (name "unconnected-(U7-NC-Pad4)") (class "Default")
      (node (ref "U7") (pin "4") (pinfunction "NC_4") (pintype "no_connect"))
    )
    (net (code "149") (name "unconnected-(U8-CPEN_N-Pad12)") (class "Default")
      (node (ref "U8") (pin "12") (pinfunction "CPEN_N_12") (pintype "bidirectional"))
    )
    (net (code "150") (name "unconnected-(U8-EXTVBUS-Pad6)") (class "Default")
      (node (ref "U8") (pin "6") (pinfunction "EXTVBUS_6") (pintype "bidirectional"))
    )
    (net (code "151") (name "unconnected-(U8-ID-Pad7)") (class "Default")
      (node (ref "U8") (pin "7") (pinfunction "ID_7") (pintype "bidirectional"))
    )
    (net (code "152") (name "unconnected-(U8-XO-Pad16)") (class "Default")
      (node (ref "U8") (pin "16") (pinfunction "XO_16") (pintype "bidirectional"))
    )
    (net (code "153") (name "unconnected-(U9-LOL-Pad26)") (class "Default")
      (node (ref "U9") (pin "26") (pinfunction "LOL_26") (pintype "bidirectional"))
    )
    (net (code "154") (name "unconnected-(U9-LOR-Pad27)") (class "Default")
      (node (ref "U9") (pin "27") (pinfunction "LOR_27") (pintype "bidirectional"))
    )
    (net (code "155") (name "unconnected-(U9-MISO{slash}MFP4-Pad15)") (class "Default")
      (node (ref "U9") (pin "15") (pinfunction "MISO/MFP4_15") (pintype "bidirectional"))
    )
    (net (code "156") (name "unconnected-(U9-SCLK{slash}MFP3-Pad12)") (class "Default")
      (node (ref "U9") (pin "12") (pinfunction "SCLK/MFP3_12") (pintype "bidirectional"))
    )
  )
)
